# USB.net
KiCad netlist of a schematic drawn in Altium Designer
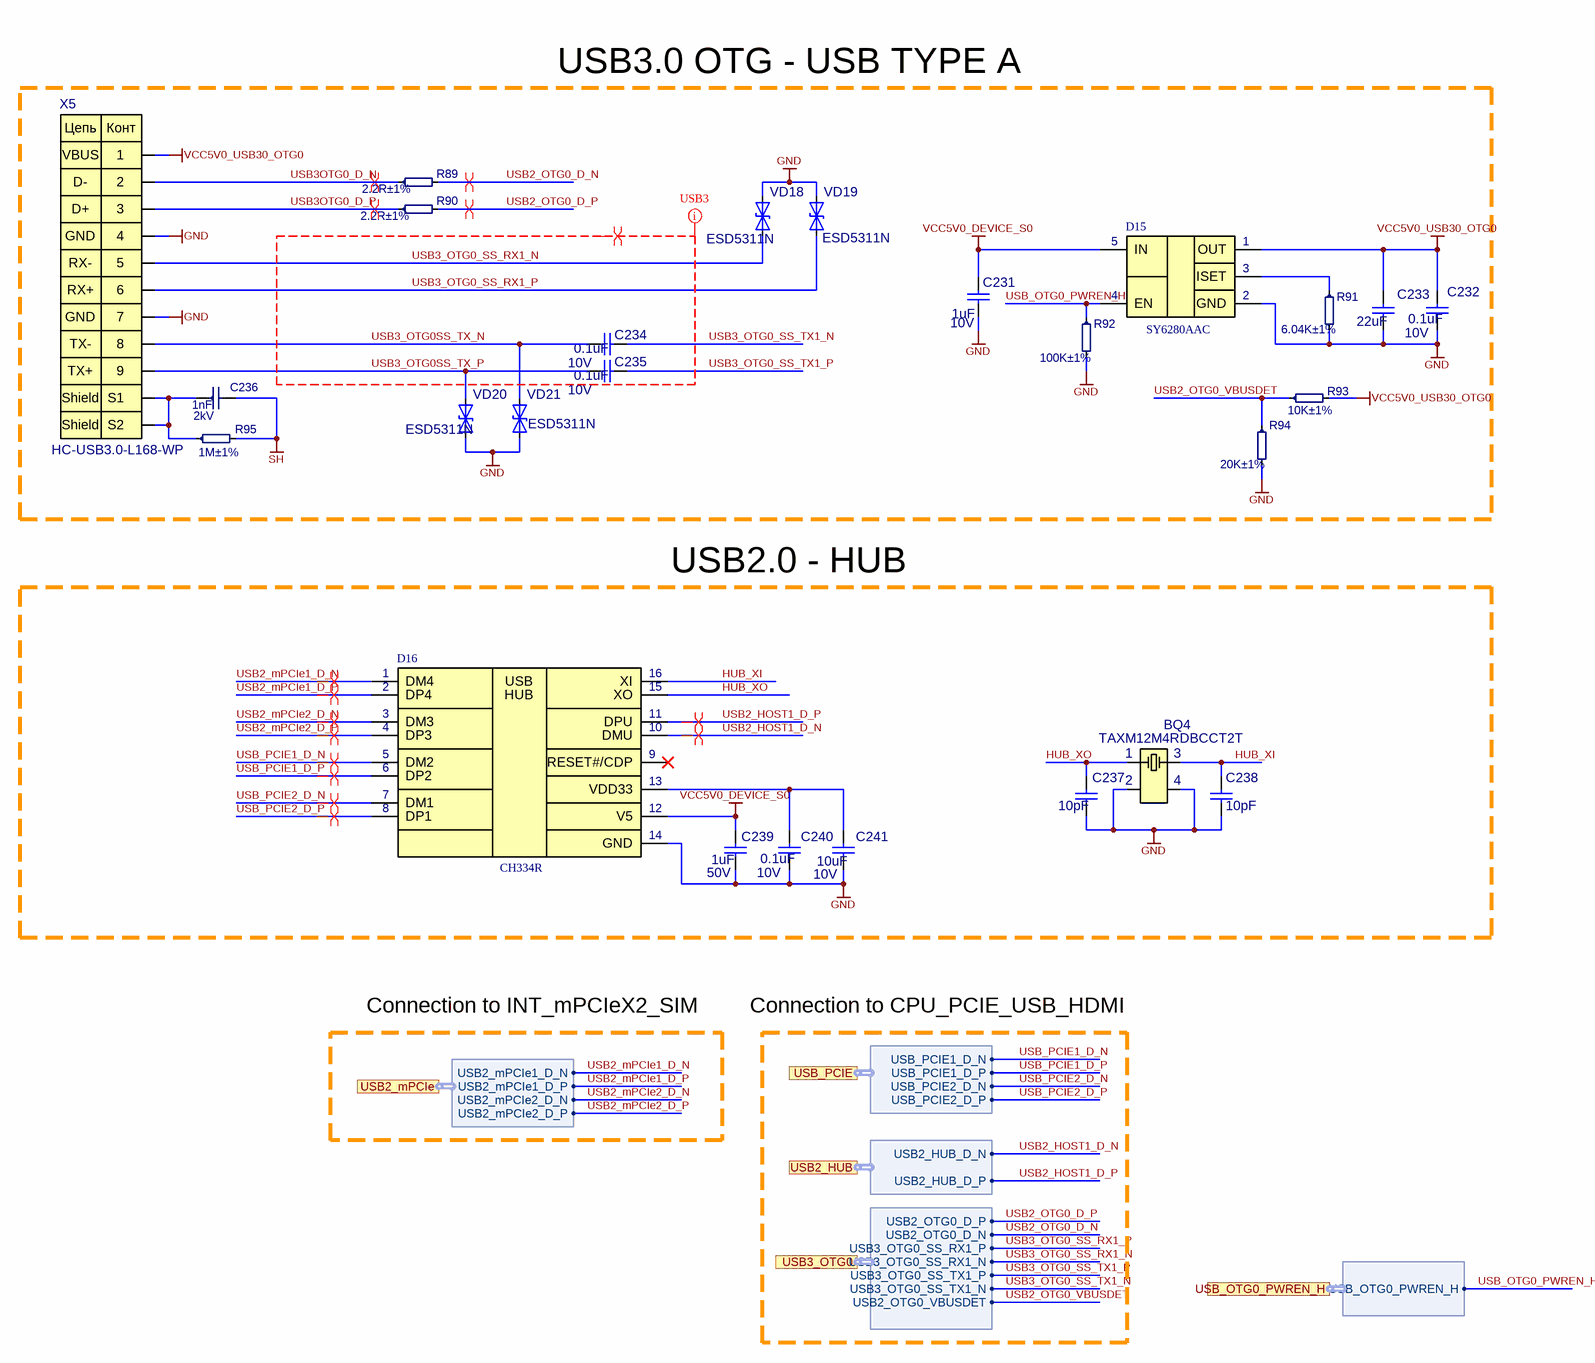
[diagram p0: USB.SchDoc]

(export (version "E")
  (design (tool "Eeschema 10.0.6"))
  (components
    (comp (ref "BQ4")
      (value "TAXM12M4RDBCCT2T")
      (footprint "XC32M4-12.000-F10NNFT")
      (description "12MHz 10pF ±10ppm SMD3225-4P")
      (fields (field (name "MANUFACTURER") "TAE"))
      (libsource (lib "LIB_RK") (part "XC32M4-12.000-F10NNFT"))
    )
    (comp (ref "C231")
      (value "1uF")
      (footprint "C0402")
      (fields
        (field (name "PART NUMBER") "0402-X5R-10V-1uF±10%")
        (field (name "VOLTAGE") "10V")
        (field (name "TOLERANCE") "10%")
        (field (name "MANUFACTURER") "Samsung")
      )
      (libsource (lib "ATB") (part "C"))
    )
    (comp (ref "C232")
      (value "0.1uF")
      (footprint "C0402")
      (fields
        (field (name "PART NUMBER") "0402-X5R-10V-0.1uF±10%")
        (field (name "VOLTAGE") "10V")
        (field (name "TOLERANCE") "10%")
        (field (name "MANUFACTURER") "Yageo")
      )
      (libsource (lib "ATB") (part "C"))
    )
    (comp (ref "C233")
      (value "22uF")
      (footprint "C0603")
      (fields
        (field (name "PART NUMBER") "0603-X5R-10V-22uF±20%")
        (field (name "VOLTAGE") "10V")
        (field (name "TOLERANCE") "20%")
      )
      (libsource (lib "ATB") (part "C"))
    )
    (comp (ref "C234")
      (value "0.1uF")
      (footprint "C0402")
      (fields
        (field (name "PART NUMBER") "0402-X5R-10V-0.1uF±10%")
        (field (name "VOLTAGE") "10V")
        (field (name "TOLERANCE") "10%")
        (field (name "MANUFACTURER") "Yageo")
      )
      (libsource (lib "") (part "C_2"))
    )
    (comp (ref "C235")
      (value "0.1uF")
      (footprint "C0402")
      (fields
        (field (name "PART NUMBER") "0402-X5R-10V-0.1uF±10%")
        (field (name "VOLTAGE") "10V")
        (field (name "TOLERANCE") "10%")
        (field (name "MANUFACTURER") "Yageo")
      )
      (libsource (lib "") (part "C_2"))
    )
    (comp (ref "C236")
      (value "1nF")
      (footprint "C1812")
      (fields
        (field (name "VOLTAGE") "2kV")
        (field (name "PART NUMBER") "1812-C0G-2kV-1nF±10%")
        (field (name "TOLERANCE") "5%")
        (field (name "MANUFACTURER") "FH")
      )
      (libsource (lib "") (part "C_1"))
    )
    (comp (ref "C237")
      (value "10pF")
      (footprint "C0402")
      (fields
        (field (name "PART NUMBER") "0402-NP0-50V-10pF±5%")
        (field (name "VOLTAGE") "50V")
        (field (name "TOLERANCE") "5%")
      )
      (libsource (lib "ATB") (part "C"))
    )
    (comp (ref "C238")
      (value "10pF")
      (footprint "C0402")
      (fields
        (field (name "PART NUMBER") "0402-NP0-50V-10pF±5%")
        (field (name "VOLTAGE") "50V")
        (field (name "TOLERANCE") "5%")
      )
      (libsource (lib "ATB") (part "C"))
    )
    (comp (ref "C239")
      (value "1uF")
      (footprint "C0603")
      (fields
        (field (name "PART NUMBER") "0603-X5R-50V-1uF±10%")
        (field (name "VOLTAGE") "50V")
        (field (name "TOLERANCE") "10%")
        (field (name "MANUFACTURER") "Yageo")
      )
      (libsource (lib "ATB") (part "C"))
    )
    (comp (ref "C240")
      (value "0.1uF")
      (footprint "C0402")
      (fields
        (field (name "PART NUMBER") "0402-X5R-10V-0.1uF±10%")
        (field (name "VOLTAGE") "10V")
        (field (name "TOLERANCE") "10%")
        (field (name "MANUFACTURER") "Yageo")
      )
      (libsource (lib "ATB") (part "C"))
    )
    (comp (ref "C241")
      (value "10uF")
      (footprint "C0402")
      (fields
        (field (name "PART NUMBER") "0402-X5R-10V-10uF±20%")
        (field (name "VOLTAGE") "10V")
        (field (name "TOLERANCE") "20%")
        (field (name "MANUFACTURER") "Murata Electronics")
      )
      (libsource (lib "ATB") (part "C"))
    )
    (comp (ref "D15")
      (value "SY6280AAC")
      (footprint "SY6280AAC")
      (description "Power Distribution Switches")
      (fields (field (name "MANUFACTURER") "Silergy Corp"))
      (libsource (lib "LIB_RK") (part "SY6280AAC"))
    )
    (comp (ref "D16")
      (value "CH334R")
      (footprint "CH334R")
      (description "4-port USB2.0 high-speed HUB controller")
      (fields (field (name "MANUFACTURER") "WCH"))
      (libsource (lib "LIB_RK") (part "CH334R"))
    )
    (comp (ref "R89")
      (value "2.2R±1%")
      (footprint "R0402")
      (fields
        (field (name "PART NUMBER") "0402-0.0625W-2.2R-100ppm±1%")
        (field (name "TOLERANCE") "1%")
        (field (name "MANUFACTURER") "Yageo")
      )
      (libsource (lib "ATB") (part "R"))
    )
    (comp (ref "R90")
      (value "2.2R±1%")
      (footprint "R0402")
      (fields
        (field (name "PART NUMBER") "0402-0.0625W-2.2R-100ppm±1%")
        (field (name "TOLERANCE") "1%")
        (field (name "MANUFACTURER") "Yageo")
      )
      (libsource (lib "ATB") (part "R"))
    )
    (comp (ref "R91")
      (value "6.04K±1%")
      (footprint "R0402")
      (fields
        (field (name "PART NUMBER") "0402-0.0625W-6.04K-100ppm±1%")
        (field (name "TOLERANCE") "1%")
        (field (name "MANUFACTURER") "Yageo")
      )
      (libsource (lib "ATB") (part "R"))
    )
    (comp (ref "R92")
      (value "100K±1%")
      (footprint "R0402")
      (description "Chip Resistor 0402 100kΩ ±1% 50V ±100ppm/℃ Thick Film")
      (fields (field (name "PART NUMBER") "0402-0.0625W-100K-100ppm±1%") (field (name "TOLERANCE") "1%"))
      (libsource (lib "ATB") (part "R"))
    )
    (comp (ref "R93")
      (value "10K±1%")
      (footprint "R0402")
      (description "Chip Resistor 0402 10kΩ ±1% 50V ±100ppm/℃ Thick Film")
      (fields (field (name "PART NUMBER") "0402-0.0625W-10K-100ppm±1%") (field (name "TOLERANCE") "1%"))
      (libsource (lib "ATB") (part "R"))
    )
    (comp (ref "R94")
      (value "20K±1%")
      (footprint "R0402")
      (description "Chip Resistor 0402 20kΩ ±1% 50V ±100ppm/℃ Thick Film")
      (fields (field (name "PART NUMBER") "0402-0.0625W-20K-100ppm±1%") (field (name "TOLERANCE") "1%"))
      (libsource (lib "ATB") (part "R"))
    )
    (comp (ref "R95")
      (value "1M±1%")
      (footprint "R1206")
      (description "Chip Resistor 1206 1MΩ ±1% 200V ±100ppm/℃ Thick Film")
      (fields (field (name "PART NUMBER") "1206-0.25W-1M-100ppm±1%") (field (name "TOLERANCE") "1%"))
      (libsource (lib "ATB") (part "R"))
    )
    (comp (ref "VD18")
      (value "ESD5311N")
      (footprint "ESD5311N")
      (description "1-Line, Bi-directional, Transient Voltage Suppressors.0.25pF.")
      (fields (field (name "MANUFACTURER") "UMW"))
      (libsource (lib "LIB_RK") (part "ESD5311N"))
    )
    (comp (ref "VD19")
      (value "ESD5311N")
      (footprint "ESD5311N")
      (description "1-Line, Bi-directional, Transient Voltage Suppressors.0.25pF.")
      (fields (field (name "MANUFACTURER") "UMW"))
      (libsource (lib "LIB_RK") (part "ESD5311N"))
    )
    (comp (ref "VD20")
      (value "ESD5311N")
      (footprint "ESD5311N")
      (description "1-Line, Bi-directional, Transient Voltage Suppressors.0.25pF.")
      (fields (field (name "MANUFACTURER") "UMW"))
      (libsource (lib "LIB_RK") (part "ESD5311N"))
    )
    (comp (ref "VD21")
      (value "ESD5311N")
      (footprint "ESD5311N")
      (description "1-Line, Bi-directional, Transient Voltage Suppressors.0.25pF.")
      (fields (field (name "MANUFACTURER") "UMW"))
      (libsource (lib "LIB_RK") (part "ESD5311N"))
    )
    (comp (ref "X5")
      (value "HC-USB3.0-L168-WP")
      (footprint "DS1095-05")
      (description "USB type A, USB 3.0, right angle")
      (fields (field (name "MANUFACTURER") "Hong Cheng"))
      (libsource (lib "ATB") (part "DS1095-05"))
    )
  )
  (nets
    (net (code "5") (name "/HUB_XI") (class "Default")
      (node (ref "BQ4") (pin "3") (pinfunction "3_3") (pintype "passive"))
      (node (ref "C238") (pin "2") (pinfunction "2_2") (pintype "passive"))
      (node (ref "D16") (pin "16") (pinfunction "XI_16") (pintype "passive"))
    )
    (net (code "6") (name "/HUB_XO") (class "Default")
      (node (ref "BQ4") (pin "1") (pinfunction "1_1") (pintype "passive"))
      (node (ref "C237") (pin "2") (pinfunction "2_2") (pintype "passive"))
      (node (ref "D16") (pin "15") (pinfunction "XO_15") (pintype "passive"))
    )
    (net (code "7") (name "/USB2_HOST1_D_N") (class "Default")
      (node (ref "D16") (pin "10") (pinfunction "DMU_10") (pintype "passive"))
    )
    (net (code "8") (name "/USB2_HOST1_D_P") (class "Default")
      (node (ref "D16") (pin "11") (pinfunction "DPU_11") (pintype "passive"))
    )
    (net (code "9") (name "/USB2_OTG0_D_N") (class "Default")
      (node (ref "R89") (pin "2") (pinfunction "2_2") (pintype "passive"))
    )
    (net (code "10") (name "/USB2_OTG0_D_P") (class "Default")
      (node (ref "R90") (pin "2") (pinfunction "2_2") (pintype "passive"))
    )
    (net (code "11") (name "/USB2_OTG0_VBUSDET") (class "Default")
      (node (ref "R93") (pin "1") (pinfunction "1_1") (pintype "passive"))
      (node (ref "R94") (pin "1") (pinfunction "1_1") (pintype "passive"))
    )
    (net (code "12") (name "/USB2_mPCIe1_D_N") (class "Default")
      (node (ref "D16") (pin "1") (pinfunction "DM4_1") (pintype "passive"))
    )
    (net (code "13") (name "/USB2_mPCIe1_D_P") (class "Default")
      (node (ref "D16") (pin "2") (pinfunction "DP4_2") (pintype "passive"))
    )
    (net (code "14") (name "/USB2_mPCIe2_D_N") (class "Default")
      (node (ref "D16") (pin "3") (pinfunction "DM3_3") (pintype "passive"))
    )
    (net (code "15") (name "/USB2_mPCIe2_D_P") (class "Default")
      (node (ref "D16") (pin "4") (pinfunction "DP3_4") (pintype "passive"))
    )
    (net (code "16") (name "/USB3OTG0_D_N") (class "Default")
      (node (ref "R89") (pin "1") (pinfunction "1_1") (pintype "passive"))
      (node (ref "X5") (pin "2") (pinfunction "2_2") (pintype "passive"))
    )
    (net (code "17") (name "/USB3OTG0_D_P") (class "Default")
      (node (ref "R90") (pin "1") (pinfunction "1_1") (pintype "passive"))
      (node (ref "X5") (pin "3") (pinfunction "3_3") (pintype "passive"))
    )
    (net (code "18") (name "/USB3_OTG0SS_TX_N") (class "Default")
      (node (ref "C234") (pin "2") (pinfunction "2_2") (pintype "passive"))
      (node (ref "VD21") (pin "2") (pinfunction "2_2") (pintype "passive"))
      (node (ref "X5") (pin "8") (pinfunction "8_8") (pintype "passive"))
    )
    (net (code "19") (name "/USB3_OTG0SS_TX_P") (class "Default")
      (node (ref "C235") (pin "2") (pinfunction "2_2") (pintype "passive"))
      (node (ref "VD20") (pin "2") (pinfunction "2_2") (pintype "passive"))
      (node (ref "X5") (pin "9") (pinfunction "9_9") (pintype "passive"))
    )
    (net (code "20") (name "/USB3_OTG0_SS_RX1_N") (class "Default")
      (node (ref "VD18") (pin "1") (pinfunction "1_1") (pintype "passive"))
      (node (ref "X5") (pin "5") (pinfunction "5_5") (pintype "passive"))
    )
    (net (code "21") (name "/USB3_OTG0_SS_RX1_P") (class "Default")
      (node (ref "VD19") (pin "1") (pinfunction "1_1") (pintype "passive"))
      (node (ref "X5") (pin "6") (pinfunction "6_6") (pintype "passive"))
    )
    (net (code "22") (name "/USB3_OTG0_SS_TX1_N") (class "Default")
      (node (ref "C234") (pin "1") (pinfunction "1_1") (pintype "passive"))
    )
    (net (code "23") (name "/USB3_OTG0_SS_TX1_P") (class "Default")
      (node (ref "C235") (pin "1") (pinfunction "1_1") (pintype "passive"))
    )
    (net (code "24") (name "/USB_OTG0_PWREN_H") (class "Default")
      (node (ref "D15") (pin "4") (pinfunction "EN_4") (pintype "passive"))
      (node (ref "R92") (pin "1") (pinfunction "1_1") (pintype "passive"))
    )
    (net (code "25") (name "/USB_PCIE1_D_N") (class "Default")
      (node (ref "D16") (pin "5") (pinfunction "DM2_5") (pintype "passive"))
    )
    (net (code "26") (name "/USB_PCIE1_D_P") (class "Default")
      (node (ref "D16") (pin "6") (pinfunction "DP2_6") (pintype "passive"))
    )
    (net (code "27") (name "/USB_PCIE2_D_N") (class "Default")
      (node (ref "D16") (pin "7") (pinfunction "DM1_7") (pintype "passive"))
    )
    (net (code "28") (name "/USB_PCIE2_D_P") (class "Default")
      (node (ref "D16") (pin "8") (pinfunction "DP1_8") (pintype "passive"))
    )
    (net (code "34") (name "GND") (class "Default")
      (node (ref "BQ4") (pin "2") (pinfunction "2_2") (pintype "passive"))
      (node (ref "BQ4") (pin "4") (pinfunction "4_4") (pintype "passive"))
      (node (ref "C231") (pin "1") (pinfunction "1_1") (pintype "passive"))
      (node (ref "C232") (pin "2") (pinfunction "2_2") (pintype "passive"))
      (node (ref "C233") (pin "1") (pinfunction "1_1") (pintype "passive"))
      (node (ref "C237") (pin "1") (pinfunction "1_1") (pintype "passive"))
      (node (ref "C238") (pin "1") (pinfunction "1_1") (pintype "passive"))
      (node (ref "C239") (pin "1") (pinfunction "1_1") (pintype "passive"))
      (node (ref "C240") (pin "2") (pinfunction "2_2") (pintype "passive"))
      (node (ref "C241") (pin "1") (pinfunction "1_1") (pintype "passive"))
      (node (ref "D15") (pin "2") (pinfunction "GND_2") (pintype "passive"))
      (node (ref "D16") (pin "14") (pinfunction "GND_14") (pintype "passive"))
      (node (ref "R91") (pin "2") (pinfunction "2_2") (pintype "passive"))
      (node (ref "R92") (pin "2") (pinfunction "2_2") (pintype "passive"))
      (node (ref "R94") (pin "2") (pinfunction "2_2") (pintype "passive"))
      (node (ref "VD18") (pin "2") (pinfunction "2_2") (pintype "passive"))
      (node (ref "VD19") (pin "2") (pinfunction "2_2") (pintype "passive"))
      (node (ref "VD20") (pin "1") (pinfunction "1_1") (pintype "passive"))
      (node (ref "VD21") (pin "1") (pinfunction "1_1") (pintype "passive"))
      (node (ref "X5") (pin "4") (pinfunction "4_4") (pintype "passive"))
      (node (ref "X5") (pin "7") (pinfunction "7_7") (pintype "passive"))
    )
    (net (code "35") (name "Net-(C236-Pad1)") (class "Default")
      (node (ref "C236") (pin "1") (pinfunction "1_1") (pintype "passive"))
      (node (ref "R95") (pin "1") (pinfunction "1_1") (pintype "passive"))
      (node (ref "X5") (pin "S1") (pinfunction "S1_S1") (pintype "passive"))
      (node (ref "X5") (pin "S2") (pinfunction "S2_S2") (pintype "passive"))
    )
    (net (code "36") (name "Net-(D15-ISET)") (class "Default")
      (node (ref "D15") (pin "3") (pinfunction "ISET_3") (pintype "passive"))
      (node (ref "R91") (pin "1") (pinfunction "1_1") (pintype "passive"))
    )
    (net (code "37") (name "Net-(D16-VDD33)") (class "Default")
      (node (ref "C240") (pin "1") (pinfunction "1_1") (pintype "passive"))
      (node (ref "C241") (pin "2") (pinfunction "2_2") (pintype "passive"))
      (node (ref "D16") (pin "13") (pinfunction "VDD33_13") (pintype "passive"))
    )
    (net (code "38") (name "SH") (class "Default")
      (node (ref "C236") (pin "2") (pinfunction "2_2") (pintype "passive"))
      (node (ref "R95") (pin "2") (pinfunction "2_2") (pintype "passive"))
    )
    (net (code "39") (name "VCC5V0_DEVICE_S0") (class "Default")
      (node (ref "C231") (pin "2") (pinfunction "2_2") (pintype "passive"))
      (node (ref "C239") (pin "2") (pinfunction "2_2") (pintype "passive"))
      (node (ref "D15") (pin "5") (pinfunction "IN_5") (pintype "passive"))
      (node (ref "D16") (pin "12") (pinfunction "V5_12") (pintype "passive"))
    )
    (net (code "40") (name "VCC5V0_USB30_OTG0") (class "Default")
      (node (ref "C232") (pin "1") (pinfunction "1_1") (pintype "passive"))
      (node (ref "C233") (pin "2") (pinfunction "2_2") (pintype "passive"))
      (node (ref "D15") (pin "1") (pinfunction "OUT_1") (pintype "passive"))
      (node (ref "R93") (pin "2") (pinfunction "2_2") (pintype "passive"))
      (node (ref "X5") (pin "1") (pinfunction "1_1") (pintype "passive"))
    )
    (net (code "41") (name "unconnected-(D16-RESET#{slash}CDP-Pad9)") (class "Default")
      (node (ref "D16") (pin "9") (pinfunction "RESET#/CDP_9") (pintype "passive+no_connect"))
    )
  )
)
